# Schematic.net
KiCad netlist of a schematic drawn in Altium Designer
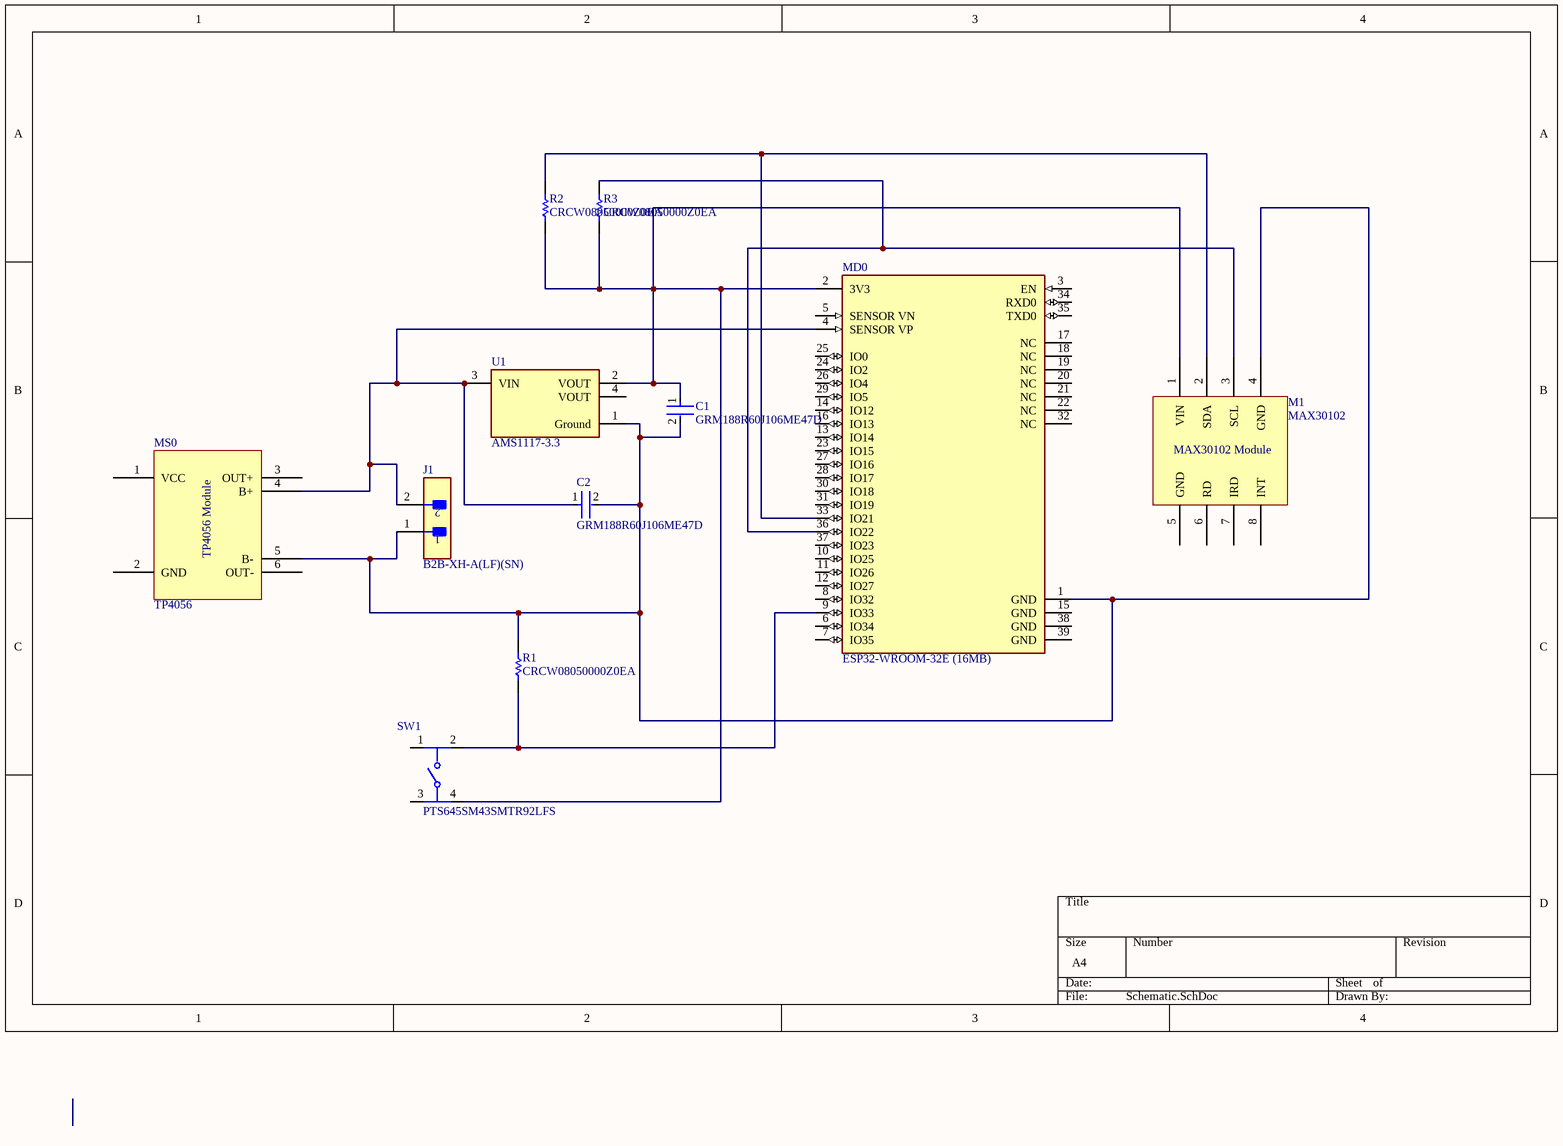
[diagram p0: Schematic.SchDoc]

(export (version "E")
  (design (tool "Eeschema 10.0.6"))
  (components
    (comp (ref "C1")
      (value "GRM188R60J106ME47D")
      (footprint "FP-GRM188-0_1-e0_2_0_55-IPC_A")
      (description "Chip Multilayer Ceramic Capacitors for General Purpose, 0603, 10uF, X5R, 15%, 20%, 6.3V")
      (fields (field (name "VOLTAGE") "6.3V") (field (name "TOLERANCE") "20%"))
      (libsource (lib "Altium Content Vault") (part "02cd4be3c70576c341d710602a673aa"))
    )
    (comp (ref "C2")
      (value "GRM188R60J106ME47D")
      (footprint "FP-GRM188-0_1-e0_2_0_55-IPC_A")
      (description "Chip Multilayer Ceramic Capacitors for General Purpose, 0603, 10uF, X5R, 15%, 20%, 6.3V")
      (fields (field (name "VOLTAGE") "6.3V") (field (name "TOLERANCE") "20%"))
      (libsource (lib "Altium Content Vault") (part "02cd4be3c70576c341d710602a673aa"))
    )
    (comp (ref "J1")
      (value "B2B-XH-A(LF)(SN)")
      (footprint "FP-B2B-XH-A_LF_SN-MFG")
      (description "CONN HEADER VERT 2POS 2.5MM")
      (libsource (lib "Altium Content Vault") (part "3bc925449376181038e59eaffc5286c"))
    )
    (comp (ref "M1")
      (value "MAX30102")
      (footprint "MAX30102 Module")
      (libsource (lib "MAX30102") (part "Component_1"))
    )
    (comp (ref "MD0")
      (value "ESP32-WROOM-32E (16MB)")
      (footprint "FP-ESP32-WROOM-32E_16MB-MFG")
      (description "RX TXRX MOD WIFI TRACE ANT SMD")
      (libsource (lib "Altium Content Vault") (part "77f46594ed2a4fcc7e275071e067929"))
    )
    (comp (ref "MS0")
      (value "TP4056")
      (footprint "TP4056 Module")
      (libsource (lib "TP4056_Module") (part "Component_1"))
    )
    (comp (ref "R1")
      (value "CRCW08050000Z0EA")
      (footprint "RESC2013X50X30LL20T20")
      (fields (field (name "MANUFACTURER") "Vishay Dale"))
      (libsource (lib "Altium Content Vault") (part "RES"))
    )
    (comp (ref "R2")
      (value "CRCW08050000Z0EA")
      (footprint "RESC2013X50X30LL20T20")
      (fields (field (name "MANUFACTURER") "Vishay Dale"))
      (libsource (lib "Altium Content Vault") (part "RES"))
    )
    (comp (ref "R3")
      (value "CRCW08050000Z0EA")
      (footprint "RESC2013X50X30LL20T20")
      (fields (field (name "MANUFACTURER") "Vishay Dale"))
      (libsource (lib "Altium Content Vault") (part "RES"))
    )
    (comp (ref "SW1")
      (value "PTS645SM43SMTR92LFS")
      (footprint "FP-PTS645SM43SMTR92LFS-MFG")
      (description "SWITCH TACTILE SPST-NO 0.05A 12V")
      (libsource (lib "Altium Content Vault") (part "1adf0dd01260c80cf25a44bfd6b99ba"))
    )
    (comp (ref "U1")
      (value "AMS1117-3.3")
      (footprint "FP-AMS1117-IPC_C")
      (description "LDO Voltage Regulators 1A, 3.3V")
      (fields
        (field (name "OCTOPART") "https://octopart.com/ams1117-3.3-advanced+monolithic+systems-25899300")
        (field (name "MANUFACTURER") "Advanced Monolithic Systems")
      )
      (libsource (lib "Altium Content Vault") (part "8bdbb5f8e77002000e30dd2845d0354"))
    )
  )
  (nets
    (net (code "1") (name "Net-(M1-SCL)") (class "Default")
      (node (ref "M1") (pin "3") (pinfunction "SCL_3") (pintype "passive"))
      (node (ref "MD0") (pin "36") (pinfunction "IO22_36") (pintype "bidirectional"))
      (node (ref "R3") (pin "2") (pinfunction "2_2") (pintype "passive"))
    )
    (net (code "2") (name "Net-(M1-SDA)") (class "Default")
      (node (ref "M1") (pin "2") (pinfunction "SDA_2") (pintype "passive"))
      (node (ref "MD0") (pin "33") (pinfunction "IO21_33") (pintype "bidirectional"))
      (node (ref "R2") (pin "2") (pinfunction "2_2") (pintype "passive"))
    )
    (net (code "3") (name "Net-(M1-VIN)") (class "Default")
      (node (ref "C1") (pin "1") (pinfunction "1_1") (pintype "passive"))
      (node (ref "M1") (pin "1") (pinfunction "VIN_1") (pintype "passive"))
      (node (ref "MD0") (pin "2") (pinfunction "3V3_2") (pintype "power_in"))
      (node (ref "R2") (pin "1") (pinfunction "1_1") (pintype "passive"))
      (node (ref "R3") (pin "1") (pinfunction "1_1") (pintype "passive"))
      (node (ref "SW1") (pin "4") (pinfunction "4_4") (pintype "passive"))
      (node (ref "U1") (pin "2") (pinfunction "VOUT_2") (pintype "passive"))
    )
    (net (code "4") (name "Net-(MD0-IO33)") (class "Default")
      (node (ref "MD0") (pin "9") (pinfunction "IO33_9") (pintype "bidirectional"))
      (node (ref "R1") (pin "1") (pinfunction "1_1") (pintype "passive"))
      (node (ref "SW1") (pin "2") (pinfunction "2_2") (pintype "passive"))
    )
    (net (code "5") (name "Net-(MD0-SENSOR_VP)") (class "Default")
      (node (ref "C2") (pin "1") (pinfunction "1_1") (pintype "passive"))
      (node (ref "J1") (pin "2") (pinfunction "2_2") (pintype "passive"))
      (node (ref "MD0") (pin "4") (pinfunction "SENSOR_VP_4") (pintype "input"))
      (node (ref "MS0") (pin "4") (pinfunction "B+_4") (pintype "passive"))
      (node (ref "U1") (pin "3") (pinfunction "VIN_3") (pintype "power_in"))
    )
    (net (code "6") (name "Net-(MS0-B-)") (class "Default")
      (node (ref "C1") (pin "2") (pinfunction "2_2") (pintype "passive"))
      (node (ref "C2") (pin "2") (pinfunction "2_2") (pintype "passive"))
      (node (ref "J1") (pin "1") (pinfunction "1_1") (pintype "passive"))
      (node (ref "M1") (pin "4") (pinfunction "GND_4") (pintype "passive"))
      (node (ref "MD0") (pin "1") (pinfunction "GND_1") (pintype "power_in"))
      (node (ref "MS0") (pin "5") (pinfunction "B-_5") (pintype "passive"))
      (node (ref "R1") (pin "2") (pinfunction "2_2") (pintype "passive"))
      (node (ref "U1") (pin "1") (pinfunction "Ground_1") (pintype "power_in"))
    )
    (net (code "7") (name "unconnected-(M1-GND-Pad5)") (class "Default")
      (node (ref "M1") (pin "5") (pinfunction "GND_5") (pintype "passive"))
    )
    (net (code "8") (name "unconnected-(M1-INT-Pad8)") (class "Default")
      (node (ref "M1") (pin "8") (pinfunction "INT_8") (pintype "passive"))
    )
    (net (code "9") (name "unconnected-(M1-IRD-Pad7)") (class "Default")
      (node (ref "M1") (pin "7") (pinfunction "IRD_7") (pintype "passive"))
    )
    (net (code "10") (name "unconnected-(M1-RD-Pad6)") (class "Default")
      (node (ref "M1") (pin "6") (pinfunction "RD_6") (pintype "passive"))
    )
    (net (code "11") (name "unconnected-(MD0-EN-Pad3)") (class "Default")
      (node (ref "MD0") (pin "3") (pinfunction "EN_3") (pintype "input"))
    )
    (net (code "12") (name "unconnected-(MD0-GND-Pad15)") (class "Default")
      (node (ref "MD0") (pin "15") (pinfunction "GND_15") (pintype "power_in"))
    )
    (net (code "13") (name "unconnected-(MD0-GND-Pad38)") (class "Default")
      (node (ref "MD0") (pin "38") (pinfunction "GND_38") (pintype "power_in"))
    )
    (net (code "14") (name "unconnected-(MD0-GND-Pad39)") (class "Default")
      (node (ref "MD0") (pin "39") (pinfunction "GND_39") (pintype "power_in"))
    )
    (net (code "15") (name "unconnected-(MD0-IO0-Pad25)") (class "Default")
      (node (ref "MD0") (pin "25") (pinfunction "IO0_25") (pintype "bidirectional"))
    )
    (net (code "16") (name "unconnected-(MD0-IO2-Pad24)") (class "Default")
      (node (ref "MD0") (pin "24") (pinfunction "IO2_24") (pintype "bidirectional"))
    )
    (net (code "17") (name "unconnected-(MD0-IO4-Pad26)") (class "Default")
      (node (ref "MD0") (pin "26") (pinfunction "IO4_26") (pintype "bidirectional"))
    )
    (net (code "18") (name "unconnected-(MD0-IO5-Pad29)") (class "Default")
      (node (ref "MD0") (pin "29") (pinfunction "IO5_29") (pintype "bidirectional"))
    )
    (net (code "19") (name "unconnected-(MD0-IO12-Pad14)") (class "Default")
      (node (ref "MD0") (pin "14") (pinfunction "IO12_14") (pintype "bidirectional"))
    )
    (net (code "20") (name "unconnected-(MD0-IO13-Pad16)") (class "Default")
      (node (ref "MD0") (pin "16") (pinfunction "IO13_16") (pintype "bidirectional"))
    )
    (net (code "21") (name "unconnected-(MD0-IO14-Pad13)") (class "Default")
      (node (ref "MD0") (pin "13") (pinfunction "IO14_13") (pintype "bidirectional"))
    )
    (net (code "22") (name "unconnected-(MD0-IO15-Pad23)") (class "Default")
      (node (ref "MD0") (pin "23") (pinfunction "IO15_23") (pintype "bidirectional"))
    )
    (net (code "23") (name "unconnected-(MD0-IO16-Pad27)") (class "Default")
      (node (ref "MD0") (pin "27") (pinfunction "IO16_27") (pintype "bidirectional"))
    )
    (net (code "24") (name "unconnected-(MD0-IO17-Pad28)") (class "Default")
      (node (ref "MD0") (pin "28") (pinfunction "IO17_28") (pintype "bidirectional"))
    )
    (net (code "25") (name "unconnected-(MD0-IO18-Pad30)") (class "Default")
      (node (ref "MD0") (pin "30") (pinfunction "IO18_30") (pintype "bidirectional"))
    )
    (net (code "26") (name "unconnected-(MD0-IO19-Pad31)") (class "Default")
      (node (ref "MD0") (pin "31") (pinfunction "IO19_31") (pintype "bidirectional"))
    )
    (net (code "27") (name "unconnected-(MD0-IO23-Pad37)") (class "Default")
      (node (ref "MD0") (pin "37") (pinfunction "IO23_37") (pintype "bidirectional"))
    )
    (net (code "28") (name "unconnected-(MD0-IO25-Pad10)") (class "Default")
      (node (ref "MD0") (pin "10") (pinfunction "IO25_10") (pintype "bidirectional"))
    )
    (net (code "29") (name "unconnected-(MD0-IO26-Pad11)") (class "Default")
      (node (ref "MD0") (pin "11") (pinfunction "IO26_11") (pintype "bidirectional"))
    )
    (net (code "30") (name "unconnected-(MD0-IO27-Pad12)") (class "Default")
      (node (ref "MD0") (pin "12") (pinfunction "IO27_12") (pintype "bidirectional"))
    )
    (net (code "31") (name "unconnected-(MD0-IO32-Pad8)") (class "Default")
      (node (ref "MD0") (pin "8") (pinfunction "IO32_8") (pintype "bidirectional"))
    )
    (net (code "32") (name "unconnected-(MD0-IO34-Pad6)") (class "Default")
      (node (ref "MD0") (pin "6") (pinfunction "IO34_6") (pintype "bidirectional"))
    )
    (net (code "33") (name "unconnected-(MD0-IO35-Pad7)") (class "Default")
      (node (ref "MD0") (pin "7") (pinfunction "IO35_7") (pintype "bidirectional"))
    )
    (net (code "34") (name "unconnected-(MD0-NC-Pad17)") (class "Default")
      (node (ref "MD0") (pin "17") (pinfunction "NC_17") (pintype "passive"))
    )
    (net (code "35") (name "unconnected-(MD0-NC-Pad18)") (class "Default")
      (node (ref "MD0") (pin "18") (pinfunction "NC_18") (pintype "passive"))
    )
    (net (code "36") (name "unconnected-(MD0-NC-Pad19)") (class "Default")
      (node (ref "MD0") (pin "19") (pinfunction "NC_19") (pintype "passive"))
    )
    (net (code "37") (name "unconnected-(MD0-NC-Pad20)") (class "Default")
      (node (ref "MD0") (pin "20") (pinfunction "NC_20") (pintype "passive"))
    )
    (net (code "38") (name "unconnected-(MD0-NC-Pad21)") (class "Default")
      (node (ref "MD0") (pin "21") (pinfunction "NC_21") (pintype "passive"))
    )
    (net (code "39") (name "unconnected-(MD0-NC-Pad22)") (class "Default")
      (node (ref "MD0") (pin "22") (pinfunction "NC_22") (pintype "passive"))
    )
    (net (code "40") (name "unconnected-(MD0-NC-Pad32)") (class "Default")
      (node (ref "MD0") (pin "32") (pinfunction "NC_32") (pintype "passive"))
    )
    (net (code "41") (name "unconnected-(MD0-RXD0-Pad34)") (class "Default")
      (node (ref "MD0") (pin "34") (pinfunction "RXD0_34") (pintype "bidirectional"))
    )
    (net (code "42") (name "unconnected-(MD0-SENSOR_VN-Pad5)") (class "Default")
      (node (ref "MD0") (pin "5") (pinfunction "SENSOR_VN_5") (pintype "input"))
    )
    (net (code "43") (name "unconnected-(MD0-TXD0-Pad35)") (class "Default")
      (node (ref "MD0") (pin "35") (pinfunction "TXD0_35") (pintype "bidirectional"))
    )
    (net (code "44") (name "unconnected-(MS0-GND-Pad2)") (class "Default")
      (node (ref "MS0") (pin "2") (pinfunction "GND_2") (pintype "passive"))
    )
    (net (code "45") (name "unconnected-(MS0-OUT+-Pad3)") (class "Default")
      (node (ref "MS0") (pin "3") (pinfunction "OUT+_3") (pintype "passive"))
    )
    (net (code "46") (name "unconnected-(MS0-OUT--Pad6)") (class "Default")
      (node (ref "MS0") (pin "6") (pinfunction "OUT-_6") (pintype "passive"))
    )
    (net (code "47") (name "unconnected-(MS0-VCC-Pad1)") (class "Default")
      (node (ref "MS0") (pin "1") (pinfunction "VCC_1") (pintype "passive"))
    )
    (net (code "48") (name "unconnected-(SW1-Pad1)") (class "Default")
      (node (ref "SW1") (pin "1") (pinfunction "1_1") (pintype "passive"))
    )
    (net (code "49") (name "unconnected-(SW1-Pad3)") (class "Default")
      (node (ref "SW1") (pin "3") (pinfunction "3_3") (pintype "passive"))
    )
    (net (code "50") (name "unconnected-(U1-VOUT-Pad4)") (class "Default")
      (node (ref "U1") (pin "4") (pinfunction "VOUT_4") (pintype "passive"))
    )
  )
)
